# converter.net
KiCad netlist of a schematic drawn in Altium Designer
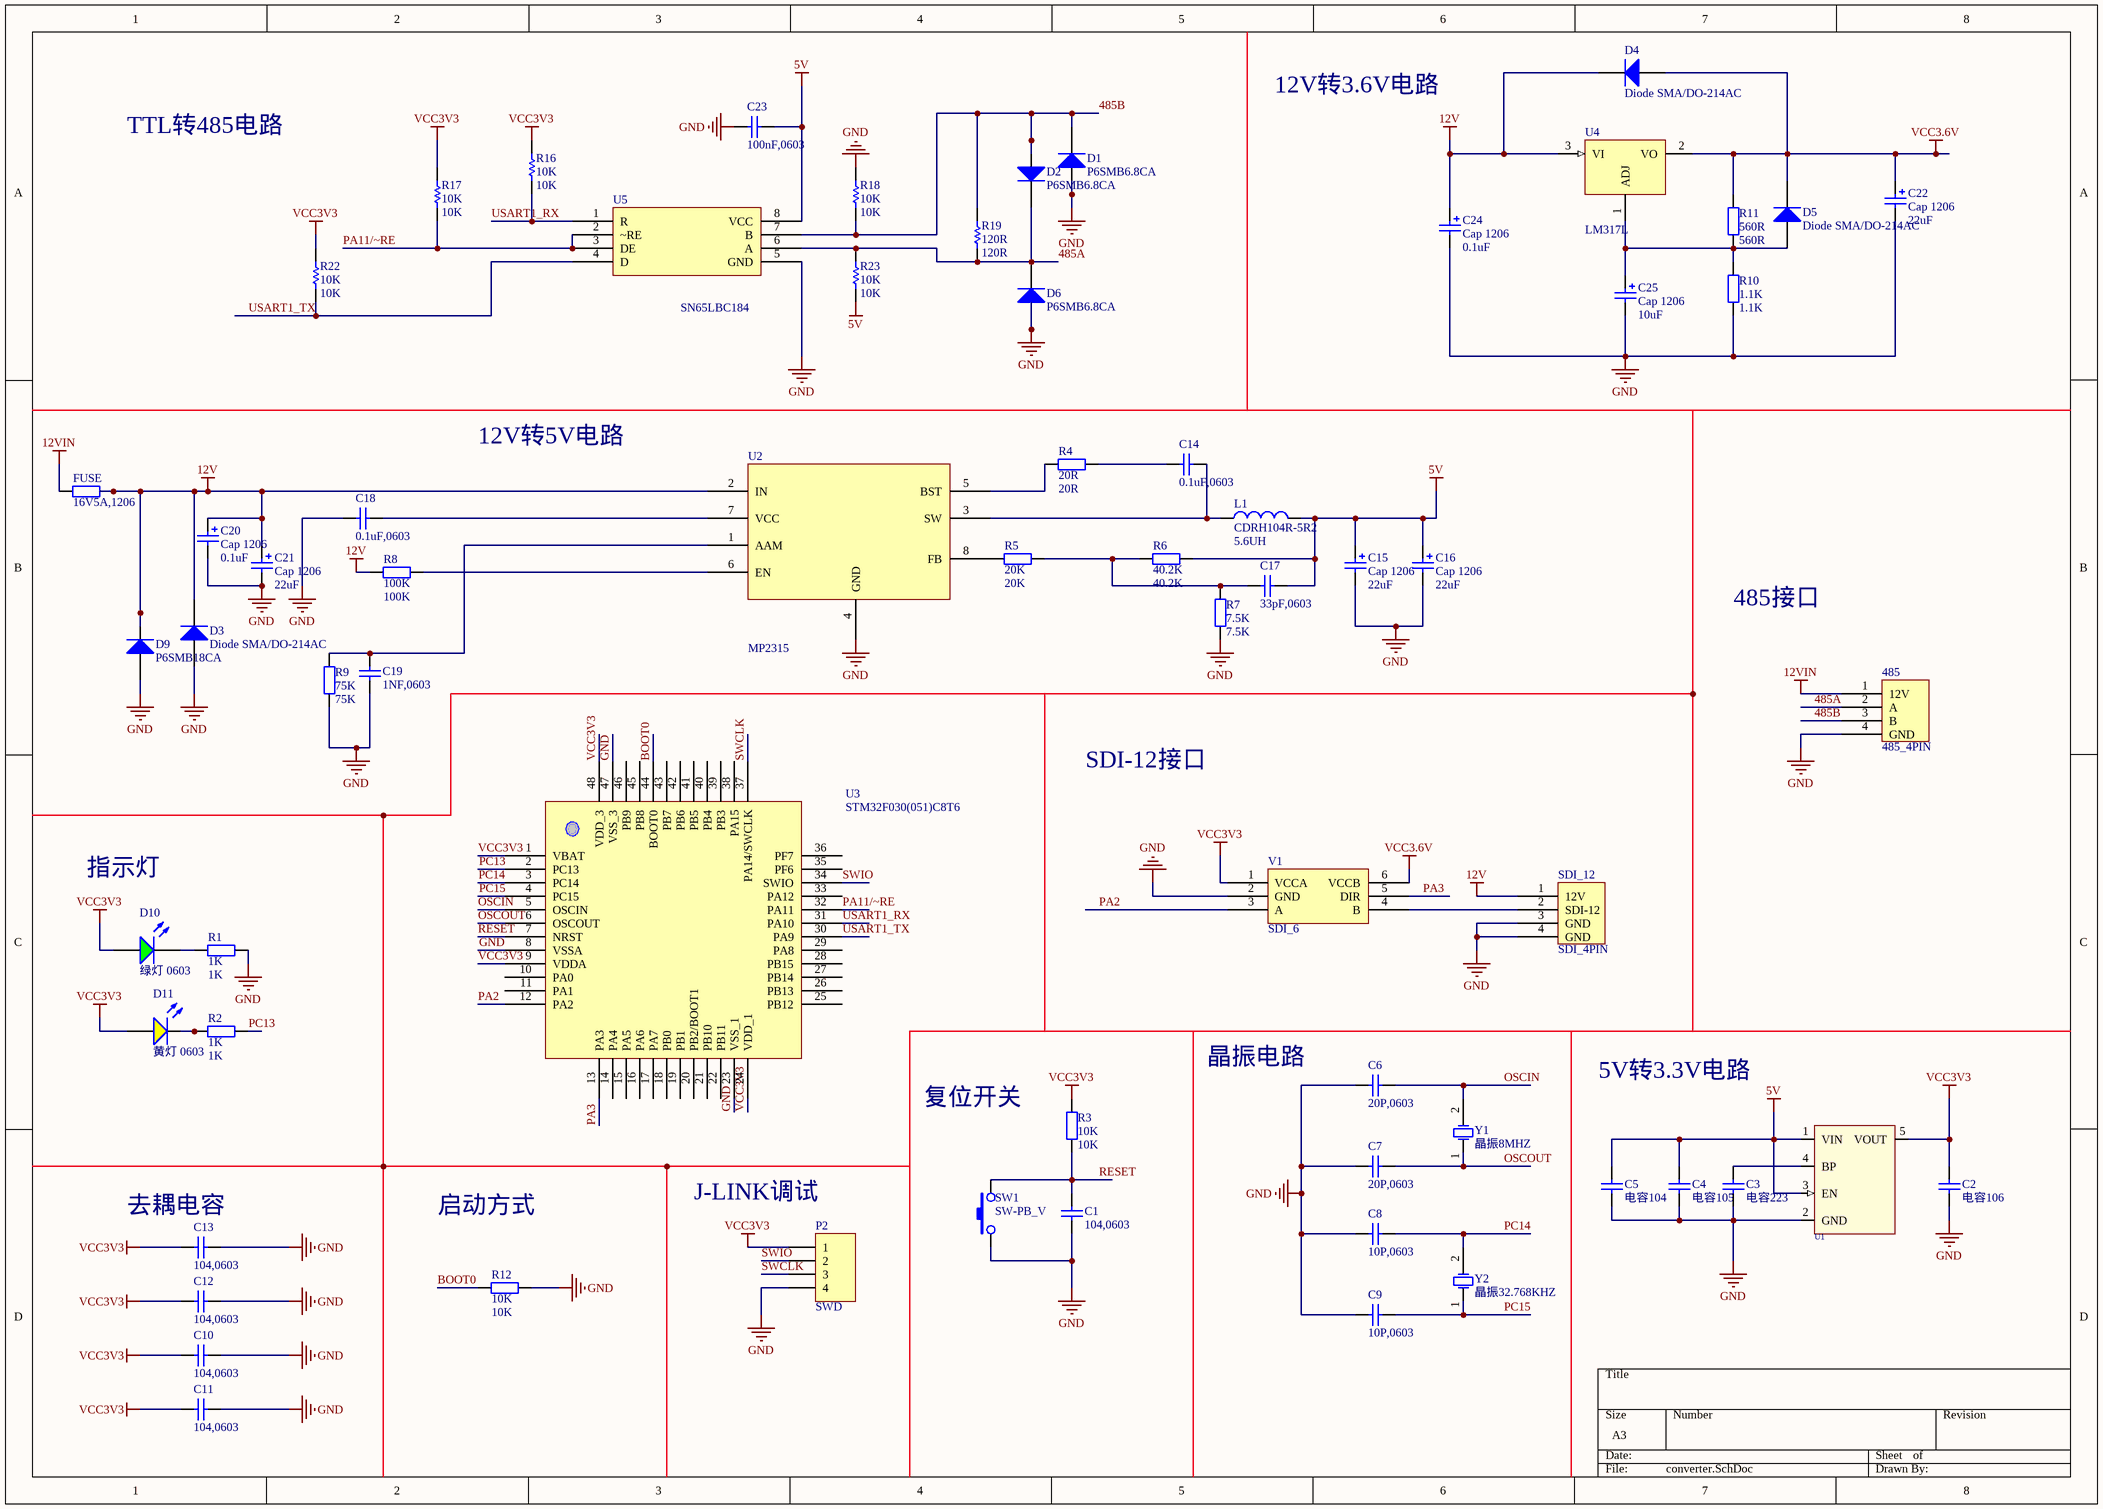
[diagram p0: converter.SchDoc]

(export (version "E")
  (design (tool "Eeschema 10.0.6"))
  (components
    (comp (ref "485") (value "485_4PIN") (footprint "HDR1X4") (libsource (lib "Schlib1") (part "485_4PIN")))
    (comp (ref "C1")
      (value "104,0603")
      (footprint "C0603")
      (description "Capacitor")
      (fields (field (name "PUBLISHER") "Altium Limited"))
      (libsource (lib "STM32F030（051）C8T6核心板--原理图库") (part "Cap"))
    )
    (comp (ref "C2")
      (value "电容106")
      (footprint "C0603")
      (description "Capacitor")
      (fields (field (name "PUBLISHER") "Altium Limited"))
      (libsource (lib "STM32F030（051）C8T6核心板--原理图库") (part "Cap"))
    )
    (comp (ref "C3")
      (value "电容223")
      (footprint "C0603")
      (description "Capacitor")
      (fields (field (name "PUBLISHER") "Altium Limited"))
      (libsource (lib "STM32F030（051）C8T6核心板--原理图库") (part "Cap"))
    )
    (comp (ref "C4")
      (value "电容105")
      (footprint "C0603")
      (description "Capacitor")
      (fields (field (name "PUBLISHER") "Altium Limited"))
      (libsource (lib "STM32F030（051）C8T6核心板--原理图库") (part "Cap"))
    )
    (comp (ref "C5")
      (value "电容104")
      (footprint "C0603")
      (description "Capacitor")
      (fields (field (name "PUBLISHER") "Altium Limited"))
      (libsource (lib "STM32F030（051）C8T6核心板--原理图库") (part "Cap"))
    )
    (comp (ref "C6")
      (value "20P,0603")
      (footprint "C0603")
      (description "Capacitor")
      (fields (field (name "PUBLISHER") "Altium Limited"))
      (libsource (lib "STM32F030（051）C8T6核心板--原理图库") (part "Cap"))
    )
    (comp (ref "C7")
      (value "20P,0603")
      (footprint "C0603")
      (description "Capacitor")
      (fields (field (name "PUBLISHER") "Altium Limited"))
      (libsource (lib "STM32F030（051）C8T6核心板--原理图库") (part "Cap"))
    )
    (comp (ref "C8")
      (value "10P,0603")
      (footprint "C0603")
      (description "Capacitor")
      (fields (field (name "PUBLISHER") "Altium Limited"))
      (libsource (lib "STM32F030（051）C8T6核心板--原理图库") (part "Cap"))
    )
    (comp (ref "C9")
      (value "10P,0603")
      (footprint "C0603")
      (description "Capacitor")
      (fields (field (name "PUBLISHER") "Altium Limited"))
      (libsource (lib "STM32F030（051）C8T6核心板--原理图库") (part "Cap"))
    )
    (comp (ref "C10")
      (value "104,0603")
      (footprint "C0603")
      (description "Capacitor")
      (fields (field (name "PUBLISHER") "Altium Limited"))
      (libsource (lib "STM32F030（051）C8T6核心板--原理图库") (part "Cap"))
    )
    (comp (ref "C11")
      (value "104,0603")
      (footprint "C0603")
      (description "Capacitor")
      (fields (field (name "PUBLISHER") "Altium Limited"))
      (libsource (lib "STM32F030（051）C8T6核心板--原理图库") (part "Cap"))
    )
    (comp (ref "C12")
      (value "104,0603")
      (footprint "C0603")
      (description "Capacitor")
      (fields (field (name "PUBLISHER") "Altium Limited"))
      (libsource (lib "STM32F030（051）C8T6核心板--原理图库") (part "Cap"))
    )
    (comp (ref "C13")
      (value "104,0603")
      (footprint "C0603")
      (description "Capacitor")
      (fields (field (name "PUBLISHER") "Altium Limited"))
      (libsource (lib "STM32F030（051）C8T6核心板--原理图库") (part "Cap"))
    )
    (comp (ref "C14")
      (value "0.1uF,0603")
      (footprint "C0603")
      (description "Capacitor")
      (fields (field (name "PUBLISHER") "Altium Limited"))
      (libsource (lib "STM32F030（051）C8T6核心板--原理图库") (part "Cap"))
    )
    (comp (ref "C15")
      (value "Cap 1206")
      (footprint "LC-1206+")
      (description "Polarized Capacitor (Axial)")
      (fields (field (name "ALTIUM_VALUE") "22uF") (field (name "PUBLISHER") "Altium Limited"))
      (libsource (lib "Miscellaneous Devices") (part "Cap Pol2"))
    )
    (comp (ref "C16")
      (value "Cap 1206")
      (footprint "LC-1206+")
      (description "Polarized Capacitor (Axial)")
      (fields (field (name "ALTIUM_VALUE") "22uF") (field (name "PUBLISHER") "Altium Limited"))
      (libsource (lib "Miscellaneous Devices") (part "Cap Pol2"))
    )
    (comp (ref "C17")
      (value "33pF,0603")
      (footprint "C0603")
      (description "Capacitor")
      (fields (field (name "PUBLISHER") "Altium Limited"))
      (libsource (lib "STM32F030（051）C8T6核心板--原理图库") (part "Cap"))
    )
    (comp (ref "C18")
      (value "0.1uF,0603")
      (footprint "C0603")
      (description "Capacitor")
      (fields (field (name "PUBLISHER") "Altium Limited"))
      (libsource (lib "STM32F030（051）C8T6核心板--原理图库") (part "Cap"))
    )
    (comp (ref "C19")
      (value "1NF,0603")
      (footprint "C0603")
      (description "Capacitor")
      (fields (field (name "PUBLISHER") "Altium Limited"))
      (libsource (lib "STM32F030（051）C8T6核心板--原理图库") (part "Cap"))
    )
    (comp (ref "C20")
      (value "Cap 1206")
      (footprint "LC-1206+")
      (description "Polarized Capacitor (Axial)")
      (fields (field (name "ALTIUM_VALUE") "0.1uF") (field (name "PUBLISHER") "Altium Limited"))
      (libsource (lib "Miscellaneous Devices") (part "Cap Pol2"))
    )
    (comp (ref "C21")
      (value "Cap 1206")
      (footprint "LC-1206+")
      (description "Polarized Capacitor (Axial)")
      (fields (field (name "ALTIUM_VALUE") "22uF") (field (name "PUBLISHER") "Altium Limited"))
      (libsource (lib "Miscellaneous Devices") (part "Cap Pol2"))
    )
    (comp (ref "C22")
      (value "Cap 1206")
      (footprint "LC-1206+")
      (description "Polarized Capacitor (Axial)")
      (fields (field (name "ALTIUM_VALUE") "22uF") (field (name "PUBLISHER") "Altium Limited"))
      (libsource (lib "Miscellaneous Devices") (part "Cap Pol2"))
    )
    (comp (ref "C23")
      (value "100nF,0603")
      (footprint "C0603")
      (description "Capacitor")
      (fields (field (name "PUBLISHER") "Altium Limited"))
      (libsource (lib "STM32F030（051）C8T6核心板--原理图库") (part "Cap"))
    )
    (comp (ref "C24")
      (value "Cap 1206")
      (footprint "LC-1206+")
      (description "Polarized Capacitor (Axial)")
      (fields (field (name "ALTIUM_VALUE") "0.1uF") (field (name "PUBLISHER") "Altium Limited"))
      (libsource (lib "Miscellaneous Devices") (part "Cap Pol2"))
    )
    (comp (ref "C25")
      (value "Cap 1206")
      (footprint "LC-1206+")
      (description "Polarized Capacitor (Axial)")
      (fields (field (name "ALTIUM_VALUE") "10uF") (field (name "PUBLISHER") "Altium Limited"))
      (libsource (lib "Miscellaneous Devices") (part "Cap Pol2"))
    )
    (comp (ref "D1")
      (value "P6SMB6.8CA")
      (footprint "LC-SMB(DO-214AA)_S1")
      (description "TVS")
      (libsource (lib "Miscellaneous Devices LC") (part "SMB/DO-214AA P6SMB6.8CA"))
    )
    (comp (ref "D2")
      (value "P6SMB6.8CA")
      (footprint "LC-SMB(DO-214AA)_S1")
      (description "TVS")
      (libsource (lib "Miscellaneous Devices LC") (part "SMB/DO-214AA P6SMB6.8CA"))
    )
    (comp (ref "D3")
      (value "Diode SMA/DO-214AC")
      (footprint "LC-SMA(DO-214AC)_S1")
      (description "1 Amp General Purpose Rectifier")
      (fields (field (name "PUBLISHER") "Altium Limited"))
      (libsource (lib "Miscellaneous Devices") (part "Diode SMB/DO-214AA"))
    )
    (comp (ref "D4")
      (value "Diode SMA/DO-214AC")
      (footprint "LC-SMA(DO-214AC)_S1")
      (description "1 Amp General Purpose Rectifier")
      (fields (field (name "PUBLISHER") "Altium Limited"))
      (libsource (lib "Miscellaneous Devices") (part "Diode 1N4001"))
    )
    (comp (ref "D5")
      (value "Diode SMA/DO-214AC")
      (footprint "LC-SMA(DO-214AC)_S1")
      (description "1 Amp General Purpose Rectifier")
      (fields (field (name "PUBLISHER") "Altium Limited"))
      (libsource (lib "Miscellaneous Devices") (part "Diode 1N4001"))
    )
    (comp (ref "D6")
      (value "P6SMB6.8CA")
      (footprint "LC-SMB(DO-214AA)_S1")
      (description "TVS")
      (libsource (lib "Miscellaneous Devices LC") (part "SMB/DO-214AA P6SMB6.8CA"))
    )
    (comp (ref "D9")
      (value "P6SMB18CA")
      (footprint "LC-SMB(DO-214AA)_S1")
      (description "TVS")
      (libsource (lib "Miscellaneous Devices LC") (part "SMB/DO-214AA P6SMB6.8CA"))
    )
    (comp (ref "D10")
      (value "绿灯 0603")
      (footprint "LC-0603_LED_S1")
      (description "发光二极管")
      (libsource (lib "Miscellaneous Devices LC") (part "0603 绿灯"))
    )
    (comp (ref "D11")
      (value "黄灯 0603")
      (footprint "LC-0603_LED_S1")
      (description "发光二极管")
      (libsource (lib "Miscellaneous Devices LC") (part "0603 黄灯"))
    )
    (comp (ref "FUSE")
      (value "16V5A,1206")
      (footprint "LC-1206_R")
      (description "贴片电阻")
      (libsource (lib "Miscellaneous Devices LC") (part "1206 180Ω (1800) 1%"))
    )
    (comp (ref "L1")
      (value "CDRH104R-5R2")
      (footprint "SMD")
      (description "Inductor")
      (fields (field (name "ALTIUM_VALUE") "5.6UH") (field (name "PUBLISHER") "Altium Limited"))
      (libsource (lib "Miscellaneous Devices") (part "Inductor"))
    )
    (comp (ref "P2")
      (value "SWD")
      (footprint "HDR1X4")
      (description "Header, 4-Pin")
      (fields (field (name "PUBLISHER") "Altium Limited"))
      (libsource (lib "Miscellaneous Connectors") (part "Header 4"))
    )
    (comp (ref "R1")
      (value "1K")
      (footprint "LC-0603_R")
      (description "Resistor")
      (fields (field (name "ALTIUM_VALUE") "1K") (field (name "PUBLISHER") "Altium Limited"))
      (libsource (lib "") (part "Res2_3"))
    )
    (comp (ref "R2")
      (value "1K")
      (footprint "LC-0603_R")
      (description "Resistor")
      (fields (field (name "ALTIUM_VALUE") "1K") (field (name "PUBLISHER") "Altium Limited"))
      (libsource (lib "") (part "Res2_3"))
    )
    (comp (ref "R3")
      (value "10K")
      (footprint "LC-0603_R")
      (description "Resistor")
      (fields (field (name "ALTIUM_VALUE") "10K") (field (name "PUBLISHER") "Altium Limited"))
      (libsource (lib "") (part "Res2_2"))
    )
    (comp (ref "R4")
      (value "20R")
      (footprint "LC-0603_R")
      (description "Resistor")
      (fields (field (name "ALTIUM_VALUE") "20R") (field (name "PUBLISHER") "Altium Limited"))
      (libsource (lib "Miscellaneous Devices") (part "Res2"))
    )
    (comp (ref "R5")
      (value "20K")
      (footprint "LC-0603_R")
      (description "Resistor")
      (fields (field (name "ALTIUM_VALUE") "20K") (field (name "PUBLISHER") "Altium Limited"))
      (libsource (lib "Miscellaneous Devices") (part "Res2"))
    )
    (comp (ref "R6")
      (value "40.2K")
      (footprint "LC-0603_R")
      (description "Resistor")
      (fields (field (name "ALTIUM_VALUE") "40.2K") (field (name "PUBLISHER") "Altium Limited"))
      (libsource (lib "Miscellaneous Devices") (part "Res2"))
    )
    (comp (ref "R7")
      (value "7.5K")
      (footprint "LC-0603_R")
      (description "Resistor")
      (fields (field (name "ALTIUM_VALUE") "7.5K") (field (name "PUBLISHER") "Altium Limited"))
      (libsource (lib "") (part "Res2_2"))
    )
    (comp (ref "R8")
      (value "100K")
      (footprint "LC-0603_R")
      (description "Resistor")
      (fields (field (name "ALTIUM_VALUE") "100K") (field (name "PUBLISHER") "Altium Limited"))
      (libsource (lib "Miscellaneous Devices") (part "Res2"))
    )
    (comp (ref "R9")
      (value "75K")
      (footprint "LC-0603_R")
      (description "Resistor")
      (fields (field (name "ALTIUM_VALUE") "75K") (field (name "PUBLISHER") "Altium Limited"))
      (libsource (lib "") (part "Res2_1"))
    )
    (comp (ref "R10")
      (value "1.1K")
      (footprint "LC-0603_R")
      (description "Resistor")
      (fields (field (name "ALTIUM_VALUE") "1.1K") (field (name "PUBLISHER") "Altium Limited"))
      (libsource (lib "") (part "Res2_1"))
    )
    (comp (ref "R11")
      (value "560R")
      (footprint "LC-0603_R")
      (description "Resistor")
      (fields (field (name "ALTIUM_VALUE") "560R") (field (name "PUBLISHER") "Altium Limited"))
      (libsource (lib "") (part "Res2_1"))
    )
    (comp (ref "R12")
      (value "10K")
      (footprint "LC-0603_R")
      (description "Resistor")
      (fields (field (name "ALTIUM_VALUE") "10K") (field (name "PUBLISHER") "Altium Limited"))
      (libsource (lib "Miscellaneous Devices") (part "Res2"))
    )
    (comp (ref "R16")
      (value "10K")
      (footprint "LC-0603_R")
      (description "Semiconductor Resistor")
      (fields (field (name "ALTIUM_VALUE") "10K") (field (name "PUBLISHER") "Altium Limited"))
      (libsource (lib "Miscellaneous Devices") (part "Res Semi"))
    )
    (comp (ref "R17")
      (value "10K")
      (footprint "LC-0603_R")
      (description "Semiconductor Resistor")
      (fields (field (name "ALTIUM_VALUE") "10K") (field (name "PUBLISHER") "Altium Limited"))
      (libsource (lib "Miscellaneous Devices") (part "Res Semi"))
    )
    (comp (ref "R18")
      (value "10K")
      (footprint "LC-0603_R")
      (description "Semiconductor Resistor")
      (fields (field (name "ALTIUM_VALUE") "10K") (field (name "PUBLISHER") "Altium Limited"))
      (libsource (lib "Miscellaneous Devices") (part "Res Semi"))
    )
    (comp (ref "R19")
      (value "120R")
      (footprint "LC-0603_R")
      (description "Semiconductor Resistor")
      (fields (field (name "ALTIUM_VALUE") "120R") (field (name "PUBLISHER") "Altium Limited"))
      (libsource (lib "Miscellaneous Devices") (part "Res Semi"))
    )
    (comp (ref "R22")
      (value "10K")
      (footprint "LC-0603_R")
      (description "Semiconductor Resistor")
      (fields (field (name "ALTIUM_VALUE") "10K") (field (name "PUBLISHER") "Altium Limited"))
      (libsource (lib "Miscellaneous Devices") (part "Res Semi"))
    )
    (comp (ref "R23")
      (value "10K")
      (footprint "LC-0603_R")
      (description "Semiconductor Resistor")
      (fields (field (name "ALTIUM_VALUE") "10K") (field (name "PUBLISHER") "Altium Limited"))
      (libsource (lib "Miscellaneous Devices") (part "Res Semi"))
    )
    (comp (ref "SDI_12")
      (value "SDI_4PIN")
      (footprint "HDR1X4")
      (libsource (lib "Schlib1") (part "SDI_4PIN"))
    )
    (comp (ref "SW1")
      (value "SW-PB_V")
      (footprint "3.8*6.1微动开关")
      (description "SWITCH")
      (libsource (lib "STM32F030（051）C8T6核心板--原理图库") (part "SW-PB_V"))
    )
    (comp (ref "U1")
      (value "RT9193")
      (fields (field (name "ICA_PARTNUM") "$$2191094$$RT9193-15CU5") (field (name "PART NUMBER") "TMP-13"))
      (libsource (lib "STM32F030（051）C8T6核心板--原理图库") (part "RT9193X_5P"))
    )
    (comp (ref "U2") (value "MP2315") (footprint "TSOT23-8") (libsource (lib "MP2315") (part "MP2315")))
    (comp (ref "U3")
      (value "STM32F030(051)C8T6")
      (footprint "48P")
      (libsource (lib "STM32F030（051）C8T6核心板--原理图库") (part "STM32F030C8T6"))
    )
    (comp (ref "U4")
      (value "LM317L")
      (footprint "TO-92-0.6")
      (description "Linear Regulator")
      (libsource (lib "General") (part "LM317L"))
    )
    (comp (ref "U5") (value "SN65LBC184") (footprint "SO8_N") (libsource (lib "串口验证") (part "SN75LBC184")))
    (comp (ref "V1") (value "SDI_6") (footprint "SOT23-6_L") (libsource (lib "Schlib1") (part "SDI_6")))
    (comp (ref "Y1")
      (value "晶振8MHZ")
      (footprint "LC-SMD-5032_2P")
      (description "贴片晶振")
      (libsource (lib "Miscellaneous Devices LC") (part "SMD-5032_2P 11.0592MHZ 20PF 20PPM"))
    )
    (comp (ref "Y2")
      (value "晶振32.768KHZ")
      (footprint "LC-SMD-3215_2P FC - 135")
      (description "贴片晶振")
      (libsource (lib "Miscellaneous Devices LC") (part "SMD-5032_2P 11.0592MHZ 20PF 20PPM"))
    )
  )
  (nets
    (net (code "1") (name "/485A") (class "Default")
      (node (ref "485") (pin "2") (pinfunction "A_2") (pintype "passive"))
      (node (ref "D2") (pin "2") (pinfunction "K_2") (pintype "passive"))
      (node (ref "D6") (pin "2") (pinfunction "K_2") (pintype "passive"))
      (node (ref "R19") (pin "1") (pinfunction "1_1") (pintype "passive"))
      (node (ref "R23") (pin "2") (pinfunction "2_2") (pintype "passive"))
      (node (ref "U5") (pin "6") (pinfunction "A_6") (pintype "passive"))
    )
    (net (code "2") (name "/485B") (class "Default")
      (node (ref "485") (pin "3") (pinfunction "B_3") (pintype "passive"))
      (node (ref "D1") (pin "2") (pinfunction "K_2") (pintype "passive"))
      (node (ref "D2") (pin "1") (pinfunction "A_1") (pintype "passive"))
      (node (ref "R18") (pin "1") (pinfunction "1_1") (pintype "passive"))
      (node (ref "R19") (pin "2") (pinfunction "2_2") (pintype "passive"))
      (node (ref "U5") (pin "7") (pinfunction "B_7") (pintype "passive"))
    )
    (net (code "3") (name "/BOOT0") (class "Default")
      (node (ref "R12") (pin "2") (pinfunction "2_2") (pintype "passive"))
      (node (ref "U3") (pin "44") (pinfunction "BOOT0_44") (pintype "passive"))
    )
    (net (code "4") (name "/OSCIN") (class "Default")
      (node (ref "C6") (pin "2") (pinfunction "2_2") (pintype "passive"))
      (node (ref "U3") (pin "5") (pinfunction "OSCIN_5") (pintype "passive"))
      (node (ref "Y1") (pin "2") (pinfunction "OSC2_2") (pintype "passive"))
    )
    (net (code "5") (name "/OSCOUT") (class "Default")
      (node (ref "C7") (pin "2") (pinfunction "2_2") (pintype "passive"))
      (node (ref "U3") (pin "6") (pinfunction "OSCOUT_6") (pintype "passive"))
      (node (ref "Y1") (pin "1") (pinfunction "OSC1_1") (pintype "passive"))
    )
    (net (code "6") (name "/PA2") (class "Default")
      (node (ref "U3") (pin "12") (pinfunction "PA2_12") (pintype "passive"))
      (node (ref "V1") (pin "3") (pinfunction "A_3") (pintype "passive"))
    )
    (net (code "7") (name "/PA3") (class "Default")
      (node (ref "U3") (pin "13") (pinfunction "PA3_13") (pintype "passive"))
      (node (ref "V1") (pin "5") (pinfunction "DIR_5") (pintype "passive"))
    )
    (net (code "8") (name "/PA11{slash}~RE") (class "Default")
      (node (ref "R17") (pin "1") (pinfunction "1_1") (pintype "passive"))
      (node (ref "U3") (pin "32") (pinfunction "PA11_32") (pintype "passive"))
      (node (ref "U5") (pin "2") (pinfunction "~RE_2") (pintype "passive"))
      (node (ref "U5") (pin "3") (pinfunction "DE_3") (pintype "passive"))
    )
    (net (code "9") (name "/PC13") (class "Default")
      (node (ref "R2") (pin "2") (pinfunction "2_2") (pintype "passive"))
      (node (ref "U3") (pin "2") (pinfunction "PC13_2") (pintype "passive"))
    )
    (net (code "10") (name "/PC14") (class "Default")
      (node (ref "C8") (pin "2") (pinfunction "2_2") (pintype "passive"))
      (node (ref "U3") (pin "3") (pinfunction "PC14_3") (pintype "passive"))
      (node (ref "Y2") (pin "2") (pinfunction "OSC2_2") (pintype "passive"))
    )
    (net (code "11") (name "/PC15") (class "Default")
      (node (ref "C9") (pin "2") (pinfunction "2_2") (pintype "passive"))
      (node (ref "U3") (pin "4") (pinfunction "PC15_4") (pintype "passive"))
      (node (ref "Y2") (pin "1") (pinfunction "OSC1_1") (pintype "passive"))
    )
    (net (code "12") (name "/RESET") (class "Default")
      (node (ref "C1") (pin "2") (pinfunction "2_2") (pintype "passive"))
      (node (ref "R3") (pin "1") (pinfunction "1_1") (pintype "passive"))
      (node (ref "SW1") (pin "2") (pinfunction "2_2") (pintype "passive"))
      (node (ref "U3") (pin "7") (pinfunction "NRST_7") (pintype "passive"))
    )
    (net (code "13") (name "/SWCLK") (class "Default")
      (node (ref "P2") (pin "3") (pinfunction "3_3") (pintype "passive"))
      (node (ref "U3") (pin "37") (pinfunction "PA14/SWCLK_37") (pintype "passive"))
    )
    (net (code "14") (name "/SWIO") (class "Default")
      (node (ref "P2") (pin "2") (pinfunction "2_2") (pintype "passive"))
      (node (ref "U3") (pin "34") (pinfunction "SWIO_34") (pintype "passive"))
    )
    (net (code "15") (name "/USART1_RX") (class "Default")
      (node (ref "R16") (pin "1") (pinfunction "1_1") (pintype "passive"))
      (node (ref "U3") (pin "31") (pinfunction "PA10_31") (pintype "passive"))
      (node (ref "U5") (pin "1") (pinfunction "R_1") (pintype "passive"))
    )
    (net (code "16") (name "/USART1_TX") (class "Default")
      (node (ref "R22") (pin "1") (pinfunction "1_1") (pintype "passive"))
      (node (ref "U3") (pin "30") (pinfunction "PA9_30") (pintype "passive"))
      (node (ref "U5") (pin "4") (pinfunction "D_4") (pintype "passive"))
    )
    (net (code "17") (name "5V") (class "Default")
      (node (ref "C15") (pin "1") (pinfunction "1_1") (pintype "passive"))
      (node (ref "C16") (pin "1") (pinfunction "1_1") (pintype "passive"))
      (node (ref "C17") (pin "2") (pinfunction "2_2") (pintype "passive"))
      (node (ref "C23") (pin "1") (pinfunction "1_1") (pintype "passive"))
      (node (ref "C4") (pin "2") (pinfunction "2_2") (pintype "passive"))
      (node (ref "C5") (pin "2") (pinfunction "2_2") (pintype "passive"))
      (node (ref "L1") (pin "2") (pinfunction "2_2") (pintype "passive"))
      (node (ref "R23") (pin "1") (pinfunction "1_1") (pintype "passive"))
      (node (ref "R6") (pin "1") (pinfunction "1_1") (pintype "passive"))
      (node (ref "U1") (pin "1") (pinfunction "VIN_1") (pintype "power_in"))
      (node (ref "U1") (pin "3") (pinfunction "EN_3") (pintype "input"))
      (node (ref "U5") (pin "8") (pinfunction "VCC_8") (pintype "passive"))
    )
    (net (code "18") (name "12V") (class "Default")
      (node (ref "C20") (pin "1") (pinfunction "1_1") (pintype "passive"))
      (node (ref "C21") (pin "1") (pinfunction "1_1") (pintype "passive"))
      (node (ref "C24") (pin "1") (pinfunction "1_1") (pintype "passive"))
      (node (ref "D3") (pin "2") (pinfunction "K_2") (pintype "passive"))
      (node (ref "D4") (pin "2") (pinfunction "K_2") (pintype "passive"))
      (node (ref "D9") (pin "2") (pinfunction "K_2") (pintype "passive"))
      (node (ref "FUSE") (pin "2") (pinfunction "2_2") (pintype "passive"))
      (node (ref "R8") (pin "2") (pinfunction "2_2") (pintype "passive"))
      (node (ref "SDI_12") (pin "1") (pinfunction "12V_1") (pintype "passive"))
      (node (ref "U2") (pin "2") (pinfunction "IN_2") (pintype "passive"))
      (node (ref "U4") (pin "3") (pinfunction "VI_3") (pintype "input"))
    )
    (net (code "19") (name "12VIN") (class "Default")
      (node (ref "485") (pin "1") (pinfunction "12V_1") (pintype "passive"))
      (node (ref "FUSE") (pin "1") (pinfunction "1_1") (pintype "passive"))
    )
    (net (code "20") (name "GND") (class "Default")
      (node (ref "485") (pin "4") (pinfunction "GND_4") (pintype "passive"))
      (node (ref "C1") (pin "1") (pinfunction "1_1") (pintype "passive"))
      (node (ref "C10") (pin "2") (pinfunction "2_2") (pintype "passive"))
      (node (ref "C11") (pin "2") (pinfunction "2_2") (pintype "passive"))
      (node (ref "C12") (pin "2") (pinfunction "2_2") (pintype "passive"))
      (node (ref "C13") (pin "2") (pinfunction "2_2") (pintype "passive"))
      (node (ref "C15") (pin "2") (pinfunction "2_2") (pintype "passive"))
      (node (ref "C16") (pin "2") (pinfunction "2_2") (pintype "passive"))
      (node (ref "C18") (pin "2") (pinfunction "2_2") (pintype "passive"))
      (node (ref "C19") (pin "2") (pinfunction "2_2") (pintype "passive"))
      (node (ref "C2") (pin "1") (pinfunction "1_1") (pintype "passive"))
      (node (ref "C20") (pin "2") (pinfunction "2_2") (pintype "passive"))
      (node (ref "C21") (pin "2") (pinfunction "2_2") (pintype "passive"))
      (node (ref "C22") (pin "2") (pinfunction "2_2") (pintype "passive"))
      (node (ref "C23") (pin "2") (pinfunction "2_2") (pintype "passive"))
      (node (ref "C24") (pin "2") (pinfunction "2_2") (pintype "passive"))
      (node (ref "C25") (pin "2") (pinfunction "2_2") (pintype "passive"))
      (node (ref "C3") (pin "1") (pinfunction "1_1") (pintype "passive"))
      (node (ref "C4") (pin "1") (pinfunction "1_1") (pintype "passive"))
      (node (ref "C5") (pin "1") (pinfunction "1_1") (pintype "passive"))
      (node (ref "C6") (pin "1") (pinfunction "1_1") (pintype "passive"))
      (node (ref "C7") (pin "1") (pinfunction "1_1") (pintype "passive"))
      (node (ref "C8") (pin "1") (pinfunction "1_1") (pintype "passive"))
      (node (ref "C9") (pin "1") (pinfunction "1_1") (pintype "passive"))
      (node (ref "D1") (pin "1") (pinfunction "A_1") (pintype "passive"))
      (node (ref "D3") (pin "1") (pinfunction "A_1") (pintype "passive"))
      (node (ref "D6") (pin "1") (pinfunction "A_1") (pintype "passive"))
      (node (ref "D9") (pin "1") (pinfunction "A_1") (pintype "passive"))
      (node (ref "P2") (pin "4") (pinfunction "4_4") (pintype "passive"))
      (node (ref "R1") (pin "2") (pinfunction "2_2") (pintype "passive"))
      (node (ref "R10") (pin "2") (pinfunction "2_2") (pintype "passive"))
      (node (ref "R12") (pin "1") (pinfunction "1_1") (pintype "passive"))
      (node (ref "R18") (pin "2") (pinfunction "2_2") (pintype "passive"))
      (node (ref "R7") (pin "1") (pinfunction "1_1") (pintype "passive"))
      (node (ref "R9") (pin "2") (pinfunction "2_2") (pintype "passive"))
      (node (ref "SDI_12") (pin "3") (pinfunction "GND_3") (pintype "passive"))
      (node (ref "SDI_12") (pin "4") (pinfunction "GND_4") (pintype "passive"))
      (node (ref "SW1") (pin "1") (pinfunction "1_1") (pintype "passive"))
      (node (ref "U1") (pin "2") (pinfunction "GND_2") (pintype "power_in"))
      (node (ref "U2") (pin "4") (pinfunction "GND_4") (pintype "passive"))
      (node (ref "U3") (pin "23") (pinfunction "VSS_1_23") (pintype "passive"))
      (node (ref "U3") (pin "47") (pinfunction "VSS_3_47") (pintype "passive"))
      (node (ref "U3") (pin "8") (pinfunction "VSSA_8") (pintype "passive"))
      (node (ref "U5") (pin "5") (pinfunction "GND_5") (pintype "passive"))
      (node (ref "V1") (pin "2") (pinfunction "GND_2") (pintype "passive"))
    )
    (net (code "21") (name "Net-(C14-Pad1)") (class "Default")
      (node (ref "C14") (pin "1") (pinfunction "1_1") (pintype "passive"))
      (node (ref "R4") (pin "1") (pinfunction "1_1") (pintype "passive"))
    )
    (net (code "22") (name "Net-(C17-Pad1)") (class "Default")
      (node (ref "C17") (pin "1") (pinfunction "1_1") (pintype "passive"))
      (node (ref "R5") (pin "1") (pinfunction "1_1") (pintype "passive"))
      (node (ref "R6") (pin "2") (pinfunction "2_2") (pintype "passive"))
      (node (ref "R7") (pin "2") (pinfunction "2_2") (pintype "passive"))
    )
    (net (code "23") (name "Net-(D5-A)") (class "Default")
      (node (ref "C25") (pin "1") (pinfunction "1_1") (pintype "passive"))
      (node (ref "D5") (pin "1") (pinfunction "A_1") (pintype "passive"))
      (node (ref "R10") (pin "1") (pinfunction "1_1") (pintype "passive"))
      (node (ref "R11") (pin "2") (pinfunction "2_2") (pintype "passive"))
      (node (ref "U4") (pin "1") (pinfunction "ADJ_1") (pintype "passive"))
    )
    (net (code "24") (name "Net-(D10-PadK)") (class "Default")
      (node (ref "D10") (pin "K") (pinfunction "K_K") (pintype "passive"))
      (node (ref "R1") (pin "1") (pinfunction "1_1") (pintype "passive"))
    )
    (net (code "25") (name "Net-(D11-PadK)") (class "Default")
      (node (ref "D11") (pin "K") (pinfunction "K_K") (pintype "passive"))
      (node (ref "R2") (pin "1") (pinfunction "1_1") (pintype "passive"))
    )
    (net (code "26") (name "Net-(SDI_12-SDI-12)") (class "Default")
      (node (ref "SDI_12") (pin "2") (pinfunction "SDI-12_2") (pintype "passive"))
      (node (ref "V1") (pin "4") (pinfunction "B_4") (pintype "passive"))
    )
    (net (code "27") (name "Net-(U1-BP)") (class "Default")
      (node (ref "C3") (pin "2") (pinfunction "2_2") (pintype "passive"))
      (node (ref "U1") (pin "4") (pinfunction "BP_4") (pintype "passive"))
    )
    (net (code "28") (name "Net-(U2-AAM)") (class "Default")
      (node (ref "C19") (pin "1") (pinfunction "1_1") (pintype "passive"))
      (node (ref "R9") (pin "1") (pinfunction "1_1") (pintype "passive"))
      (node (ref "U2") (pin "1") (pinfunction "AAM_1") (pintype "passive"))
    )
    (net (code "29") (name "Net-(U2-BST)") (class "Default")
      (node (ref "R4") (pin "2") (pinfunction "2_2") (pintype "passive"))
      (node (ref "U2") (pin "5") (pinfunction "BST_5") (pintype "passive"))
    )
    (net (code "30") (name "Net-(U2-EN)") (class "Default")
      (node (ref "R8") (pin "1") (pinfunction "1_1") (pintype "passive"))
      (node (ref "U2") (pin "6") (pinfunction "EN_6") (pintype "passive"))
    )
    (net (code "31") (name "Net-(U2-FB)") (class "Default")
      (node (ref "R5") (pin "2") (pinfunction "2_2") (pintype "passive"))
      (node (ref "U2") (pin "8") (pinfunction "FB_8") (pintype "passive"))
    )
    (net (code "32") (name "Net-(U2-SW)") (class "Default")
      (node (ref "C14") (pin "2") (pinfunction "2_2") (pintype "passive"))
      (node (ref "L1") (pin "1") (pinfunction "1_1") (pintype "passive"))
      (node (ref "U2") (pin "3") (pinfunction "SW_3") (pintype "passive"))
    )
    (net (code "33") (name "Net-(U2-VCC)") (class "Default")
      (node (ref "C18") (pin "1") (pinfunction "1_1") (pintype "passive"))
      (node (ref "U2") (pin "7") (pinfunction "VCC_7") (pintype "passive"))
    )
    (net (code "34") (name "VCC3.6V") (class "Default")
      (node (ref "C22") (pin "1") (pinfunction "1_1") (pintype "passive"))
      (node (ref "D4") (pin "1") (pinfunction "A_1") (pintype "passive"))
      (node (ref "D5") (pin "2") (pinfunction "K_2") (pintype "passive"))
      (node (ref "R11") (pin "1") (pinfunction "1_1") (pintype "passive"))
      (node (ref "U4") (pin "2") (pinfunction "VO_2") (pintype "power_in"))
      (node (ref "V1") (pin "6") (pinfunction "VCCB_6") (pintype "passive"))
    )
    (net (code "35") (name "VCC3V3") (class "Default")
      (node (ref "C10") (pin "1") (pinfunction "1_1") (pintype "passive"))
      (node (ref "C11") (pin "1") (pinfunction "1_1") (pintype "passive"))
      (node (ref "C12") (pin "1") (pinfunction "1_1") (pintype "passive"))
      (node (ref "C13") (pin "1") (pinfunction "1_1") (pintype "passive"))
      (node (ref "C2") (pin "2") (pinfunction "2_2") (pintype "passive"))
      (node (ref "D10") (pin "A") (pinfunction "A_A") (pintype "passive"))
      (node (ref "D11") (pin "A") (pinfunction "A_A") (pintype "passive"))
      (node (ref "P2") (pin "1") (pinfunction "1_1") (pintype "passive"))
      (node (ref "R16") (pin "2") (pinfunction "2_2") (pintype "passive"))
      (node (ref "R17") (pin "2") (pinfunction "2_2") (pintype "passive"))
      (node (ref "R22") (pin "2") (pinfunction "2_2") (pintype "passive"))
      (node (ref "R3") (pin "2") (pinfunction "2_2") (pintype "passive"))
      (node (ref "U1") (pin "5") (pinfunction "VOUT_5") (pintype "power_in"))
      (node (ref "U3") (pin "1") (pinfunction "VBAT_1") (pintype "passive"))
      (node (ref "U3") (pin "24") (pinfunction "VDD_1_24") (pintype "passive"))
      (node (ref "U3") (pin "48") (pinfunction "VDD_3_48") (pintype "passive"))
      (node (ref "U3") (pin "9") (pinfunction "VDDA_9") (pintype "passive"))
      (node (ref "V1") (pin "1") (pinfunction "VCCA_1") (pintype "passive"))
    )
    (net (code "36") (name "unconnected-(U3-PA0-Pad10)") (class "Default")
      (node (ref "U3") (pin "10") (pinfunction "PA0_10") (pintype "passive"))
    )
    (net (code "37") (name "unconnected-(U3-PA1-Pad11)") (class "Default")
      (node (ref "U3") (pin "11") (pinfunction "PA1_11") (pintype "passive"))
    )
    (net (code "38") (name "unconnected-(U3-PA4-Pad14)") (class "Default")
      (node (ref "U3") (pin "14") (pinfunction "PA4_14") (pintype "passive"))
    )
    (net (code "39") (name "unconnected-(U3-PA5-Pad15)") (class "Default")
      (node (ref "U3") (pin "15") (pinfunction "PA5_15") (pintype "passive"))
    )
    (net (code "40") (name "unconnected-(U3-PA6-Pad16)") (class "Default")
      (node (ref "U3") (pin "16") (pinfunction "PA6_16") (pintype "passive"))
    )
    (net (code "41") (name "unconnected-(U3-PA7-Pad17)") (class "Default")
      (node (ref "U3") (pin "17") (pinfunction "PA7_17") (pintype "passive"))
    )
    (net (code "42") (name "unconnected-(U3-PA8-Pad29)") (class "Default")
      (node (ref "U3") (pin "29") (pinfunction "PA8_29") (pintype "passive"))
    )
    (net (code "43") (name "unconnected-(U3-PA12-Pad33)") (class "Default")
      (node (ref "U3") (pin "33") (pinfunction "PA12_33") (pintype "passive"))
    )
    (net (code "44") (name "unconnected-(U3-PA15-Pad38)") (class "Default")
      (node (ref "U3") (pin "38") (pinfunction "PA15_38") (pintype "passive"))
    )
    (net (code "45") (name "unconnected-(U3-PB0-Pad18)") (class "Default")
      (node (ref "U3") (pin "18") (pinfunction "PB0_18") (pintype "passive"))
    )
    (net (code "46") (name "unconnected-(U3-PB1-Pad19)") (class "Default")
      (node (ref "U3") (pin "19") (pinfunction "PB1_19") (pintype "passive"))
    )
    (net (code "47") (name "unconnected-(U3-PB2{slash}BOOT1-Pad20)") (class "Default")
      (node (ref "U3") (pin "20") (pinfunction "PB2/BOOT1_20") (pintype "passive"))
    )
    (net (code "48") (name "unconnected-(U3-PB3-Pad39)") (class "Default")
      (node (ref "U3") (pin "39") (pinfunction "PB3_39") (pintype "passive"))
    )
    (net (code "49") (name "unconnected-(U3-PB4-Pad40)") (class "Default")
      (node (ref "U3") (pin "40") (pinfunction "PB4_40") (pintype "passive"))
    )
    (net (code "50") (name "unconnected-(U3-PB5-Pad41)") (class "Default")
      (node (ref "U3") (pin "41") (pinfunction "PB5_41") (pintype "passive"))
    )
    (net (code "51") (name "unconnected-(U3-PB6-Pad42)") (class "Default")
      (node (ref "U3") (pin "42") (pinfunction "PB6_42") (pintype "passive"))
    )
    (net (code "52") (name "unconnected-(U3-PB7-Pad43)") (class "Default")
      (node (ref "U3") (pin "43") (pinfunction "PB7_43") (pintype "passive"))
    )
    (net (code "53") (name "unconnected-(U3-PB8-Pad45)") (class "Default")
      (node (ref "U3") (pin "45") (pinfunction "PB8_45") (pintype "passive"))
    )
    (net (code "54") (name "unconnected-(U3-PB9-Pad46)") (class "Default")
      (node (ref "U3") (pin "46") (pinfunction "PB9_46") (pintype "passive"))
    )
    (net (code "55") (name "unconnected-(U3-PB10-Pad21)") (class "Default")
      (node (ref "U3") (pin "21") (pinfunction "PB10_21") (pintype "passive"))
    )
    (net (code "56") (name "unconnected-(U3-PB11-Pad22)") (class "Default")
      (node (ref "U3") (pin "22") (pinfunction "PB11_22") (pintype "passive"))
    )
    (net (code "57") (name "unconnected-(U3-PB12-Pad25)") (class "Default")
      (node (ref "U3") (pin "25") (pinfunction "PB12_25") (pintype "passive"))
    )
    (net (code "58") (name "unconnected-(U3-PB13-Pad26)") (class "Default")
      (node (ref "U3") (pin "26") (pinfunction "PB13_26") (pintype "passive"))
    )
    (net (code "59") (name "unconnected-(U3-PB14-Pad27)") (class "Default")
      (node (ref "U3") (pin "27") (pinfunction "PB14_27") (pintype "passive"))
    )
    (net (code "60") (name "unconnected-(U3-PB15-Pad28)") (class "Default")
      (node (ref "U3") (pin "28") (pinfunction "PB15_28") (pintype "passive"))
    )
    (net (code "61") (name "unconnected-(U3-PF6-Pad35)") (class "Default")
      (node (ref "U3") (pin "35") (pinfunction "PF6_35") (pintype "passive"))
    )
    (net (code "62") (name "unconnected-(U3-PF7-Pad36)") (class "Default")
      (node (ref "U3") (pin "36") (pinfunction "PF7_36") (pintype "passive"))
    )
  )
)
